# schematic.net
KiCad netlist of a schematic drawn in EAGLE
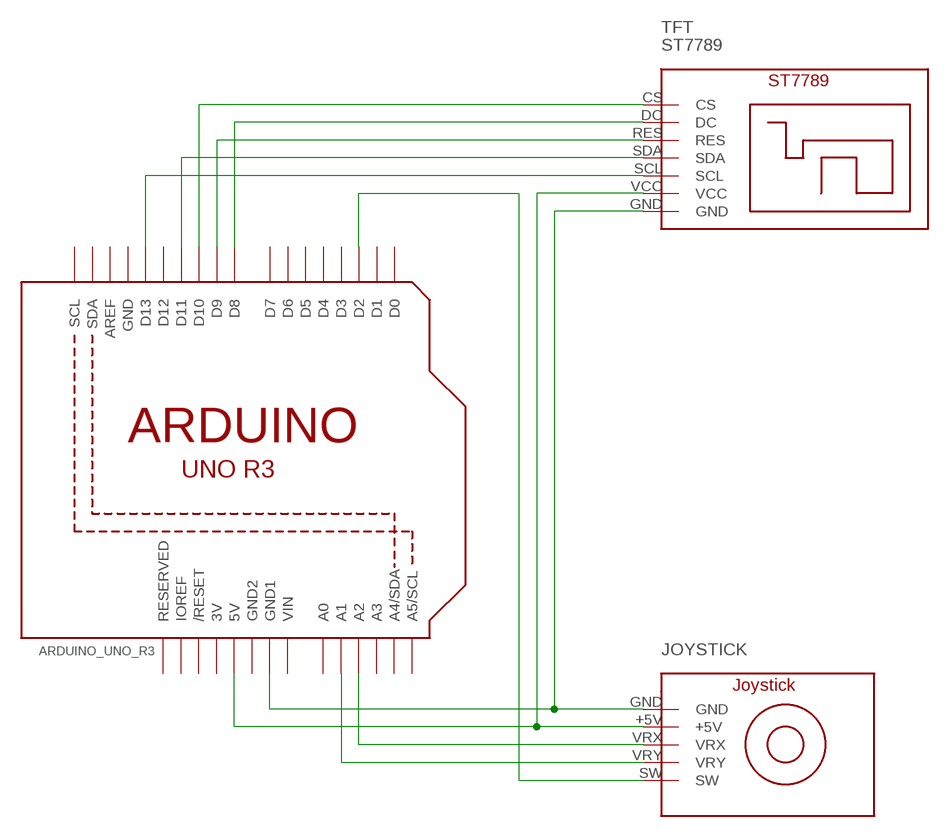
[diagram p0: schematic, sheet 1]

(export (version "E")
  (design (tool "Eeschema 10.0.6"))
  (components
    (comp (ref "ARDUINO_UNO_R3")
      (value "ARDUINOR3-BPLACE")
      (footprint "eagle-import:ARDUINOR3-BPLACE")
      (libsource (lib "eagle-import") (part "ARDUINOR3-BPLACE"))
    )
    (comp (ref "JOYSTICK")
      (value "JOYSTICK")
      (footprint "eagle-import:FP_JOYSTICK")
      (libsource (lib "eagle-import") (part "JOYSTICK"))
    )
    (comp (ref "U$1")
      (value "ST7789")
      (footprint "eagle-import:FP_ST7789")
      (libsource (lib "eagle-import") (part "ST7789"))
    )
  )
  (nets
    (net (code "1") (name "/3V") (class "Default")
      (node (ref "ARDUINO_UNO_R3") (pin "3V") (pinfunction "3V_3V") (pintype "power_in"))
    )
    (net (code "2") (name "/GND") (class "Default")
      (node (ref "ARDUINO_UNO_R3") (pin "GND") (pinfunction "GND_GND") (pintype "power_in"))
    )
    (net (code "3") (name "/GND2") (class "Default")
      (node (ref "ARDUINO_UNO_R3") (pin "GND2") (pinfunction "GND2_GND2") (pintype "power_in"))
    )
    (net (code "4") (name "/VIN") (class "Default")
      (node (ref "ARDUINO_UNO_R3") (pin "VIN") (pinfunction "VIN_VIN") (pintype "power_in"))
    )
    (net (code "5") (name "Net-(ARDUINO_UNO_R3-Pad5V)") (class "Default")
      (node (ref "ARDUINO_UNO_R3") (pin "5V") (pinfunction "5V_5V") (pintype "power_in"))
      (node (ref "JOYSTICK") (pin "+5V") (pinfunction "+5V_+5V") (pintype "bidirectional"))
      (node (ref "U$1") (pin "VCC") (pinfunction "VCC_VCC") (pintype "bidirectional"))
    )
    (net (code "6") (name "Net-(ARDUINO_UNO_R3-PadA1)") (class "Default")
      (node (ref "ARDUINO_UNO_R3") (pin "A1") (pinfunction "A1_A1") (pintype "bidirectional"))
      (node (ref "JOYSTICK") (pin "VRY") (pinfunction "VRY_VRY") (pintype "bidirectional"))
    )
    (net (code "7") (name "Net-(ARDUINO_UNO_R3-PadA2)") (class "Default")
      (node (ref "ARDUINO_UNO_R3") (pin "A2") (pinfunction "A2_A2") (pintype "bidirectional"))
      (node (ref "JOYSTICK") (pin "VRX") (pinfunction "VRX_VRX") (pintype "bidirectional"))
    )
    (net (code "8") (name "Net-(ARDUINO_UNO_R3-PadD2)") (class "Default")
      (node (ref "ARDUINO_UNO_R3") (pin "D2") (pinfunction "D2_D2") (pintype "bidirectional"))
      (node (ref "JOYSTICK") (pin "SW") (pinfunction "SW_SW") (pintype "bidirectional"))
    )
    (net (code "9") (name "Net-(ARDUINO_UNO_R3-PadD8)") (class "Default")
      (node (ref "ARDUINO_UNO_R3") (pin "D8") (pinfunction "D8_D8") (pintype "bidirectional"))
      (node (ref "U$1") (pin "DC") (pinfunction "DC_DC") (pintype "bidirectional"))
    )
    (net (code "10") (name "Net-(ARDUINO_UNO_R3-PadD9)") (class "Default")
      (node (ref "ARDUINO_UNO_R3") (pin "D9") (pinfunction "D9_D9") (pintype "bidirectional"))
      (node (ref "U$1") (pin "RES") (pinfunction "RES_RES") (pintype "bidirectional"))
    )
    (net (code "11") (name "Net-(ARDUINO_UNO_R3-PadD10)") (class "Default")
      (node (ref "ARDUINO_UNO_R3") (pin "D10") (pinfunction "D10_D10") (pintype "bidirectional"))
      (node (ref "U$1") (pin "CS") (pinfunction "CS_CS") (pintype "bidirectional"))
    )
    (net (code "12") (name "Net-(ARDUINO_UNO_R3-PadD11)") (class "Default")
      (node (ref "ARDUINO_UNO_R3") (pin "D11") (pinfunction "D11_D11") (pintype "bidirectional"))
      (node (ref "U$1") (pin "SDA") (pinfunction "SDA_SDA") (pintype "bidirectional"))
    )
    (net (code "13") (name "Net-(ARDUINO_UNO_R3-PadD13)") (class "Default")
      (node (ref "ARDUINO_UNO_R3") (pin "D13") (pinfunction "D13_D13") (pintype "bidirectional"))
      (node (ref "U$1") (pin "SCL") (pinfunction "SCL_SCL") (pintype "bidirectional"))
    )
    (net (code "14") (name "Net-(ARDUINO_UNO_R3-PadGND1)") (class "Default")
      (node (ref "ARDUINO_UNO_R3") (pin "GND1") (pinfunction "GND1_GND1") (pintype "power_in"))
      (node (ref "JOYSTICK") (pin "GND") (pinfunction "GND_GND") (pintype "bidirectional"))
      (node (ref "U$1") (pin "GND") (pinfunction "GND_GND") (pintype "bidirectional"))
    )
    (net (code "15") (name "unconnected-(ARDUINO_UNO_R3-A4{slash}SDA-PadA4)") (class "Default")
      (node (ref "ARDUINO_UNO_R3") (pin "A4") (pinfunction "A4/SDA_A4") (pintype "bidirectional"))
    )
    (net (code "16") (name "unconnected-(ARDUINO_UNO_R3-A5{slash}SCL-PadA5)") (class "Default")
      (node (ref "ARDUINO_UNO_R3") (pin "A5") (pinfunction "A5/SCL_A5") (pintype "bidirectional"))
    )
    (net (code "17") (name "unconnected-(ARDUINO_UNO_R3-PadA0)") (class "Default")
      (node (ref "ARDUINO_UNO_R3") (pin "A0") (pinfunction "A0_A0") (pintype "bidirectional"))
    )
    (net (code "18") (name "unconnected-(ARDUINO_UNO_R3-PadA3)") (class "Default")
      (node (ref "ARDUINO_UNO_R3") (pin "A3") (pinfunction "A3_A3") (pintype "bidirectional"))
    )
    (net (code "19") (name "unconnected-(ARDUINO_UNO_R3-PadAREF)") (class "Default")
      (node (ref "ARDUINO_UNO_R3") (pin "AREF") (pinfunction "AREF_AREF") (pintype "bidirectional"))
    )
    (net (code "20") (name "unconnected-(ARDUINO_UNO_R3-PadD0)") (class "Default")
      (node (ref "ARDUINO_UNO_R3") (pin "D0") (pinfunction "D0_D0") (pintype "bidirectional"))
    )
    (net (code "21") (name "unconnected-(ARDUINO_UNO_R3-PadD1)") (class "Default")
      (node (ref "ARDUINO_UNO_R3") (pin "D1") (pinfunction "D1_D1") (pintype "bidirectional"))
    )
    (net (code "22") (name "unconnected-(ARDUINO_UNO_R3-PadD3)") (class "Default")
      (node (ref "ARDUINO_UNO_R3") (pin "D3") (pinfunction "D3_D3") (pintype "bidirectional"))
    )
    (net (code "23") (name "unconnected-(ARDUINO_UNO_R3-PadD4)") (class "Default")
      (node (ref "ARDUINO_UNO_R3") (pin "D4") (pinfunction "D4_D4") (pintype "bidirectional"))
    )
    (net (code "24") (name "unconnected-(ARDUINO_UNO_R3-PadD5)") (class "Default")
      (node (ref "ARDUINO_UNO_R3") (pin "D5") (pinfunction "D5_D5") (pintype "bidirectional"))
    )
    (net (code "25") (name "unconnected-(ARDUINO_UNO_R3-PadD6)") (class "Default")
      (node (ref "ARDUINO_UNO_R3") (pin "D6") (pinfunction "D6_D6") (pintype "bidirectional"))
    )
    (net (code "26") (name "unconnected-(ARDUINO_UNO_R3-PadD7)") (class "Default")
      (node (ref "ARDUINO_UNO_R3") (pin "D7") (pinfunction "D7_D7") (pintype "bidirectional"))
    )
    (net (code "27") (name "unconnected-(ARDUINO_UNO_R3-PadD12)") (class "Default")
      (node (ref "ARDUINO_UNO_R3") (pin "D12") (pinfunction "D12_D12") (pintype "bidirectional"))
    )
    (net (code "28") (name "unconnected-(ARDUINO_UNO_R3-PadIOREF)") (class "Default")
      (node (ref "ARDUINO_UNO_R3") (pin "IOREF") (pinfunction "IOREF_IOREF") (pintype "output"))
    )
    (net (code "29") (name "unconnected-(ARDUINO_UNO_R3-PadRESERVED)") (class "Default")
      (node (ref "ARDUINO_UNO_R3") (pin "RESERVED") (pinfunction "RESERVED_RESERVED") (pintype "no_connect"))
    )
    (net (code "30") (name "unconnected-(ARDUINO_UNO_R3-PadSCL)") (class "Default")
      (node (ref "ARDUINO_UNO_R3") (pin "SCL") (pinfunction "SCL_SCL") (pintype "bidirectional"))
    )
    (net (code "31") (name "unconnected-(ARDUINO_UNO_R3-PadSDA)") (class "Default")
      (node (ref "ARDUINO_UNO_R3") (pin "SDA") (pinfunction "SDA_SDA") (pintype "bidirectional"))
    )
    (net (code "32") (name "unconnected-(ARDUINO_UNO_R3-{slash}RESET-PadRESET)") (class "Default")
      (node (ref "ARDUINO_UNO_R3") (pin "RESET") (pinfunction "/RESET_RESET") (pintype "bidirectional"))
    )
  )
)
